# vichaarak.net
KiCad netlist of a schematic drawn in EAGLE
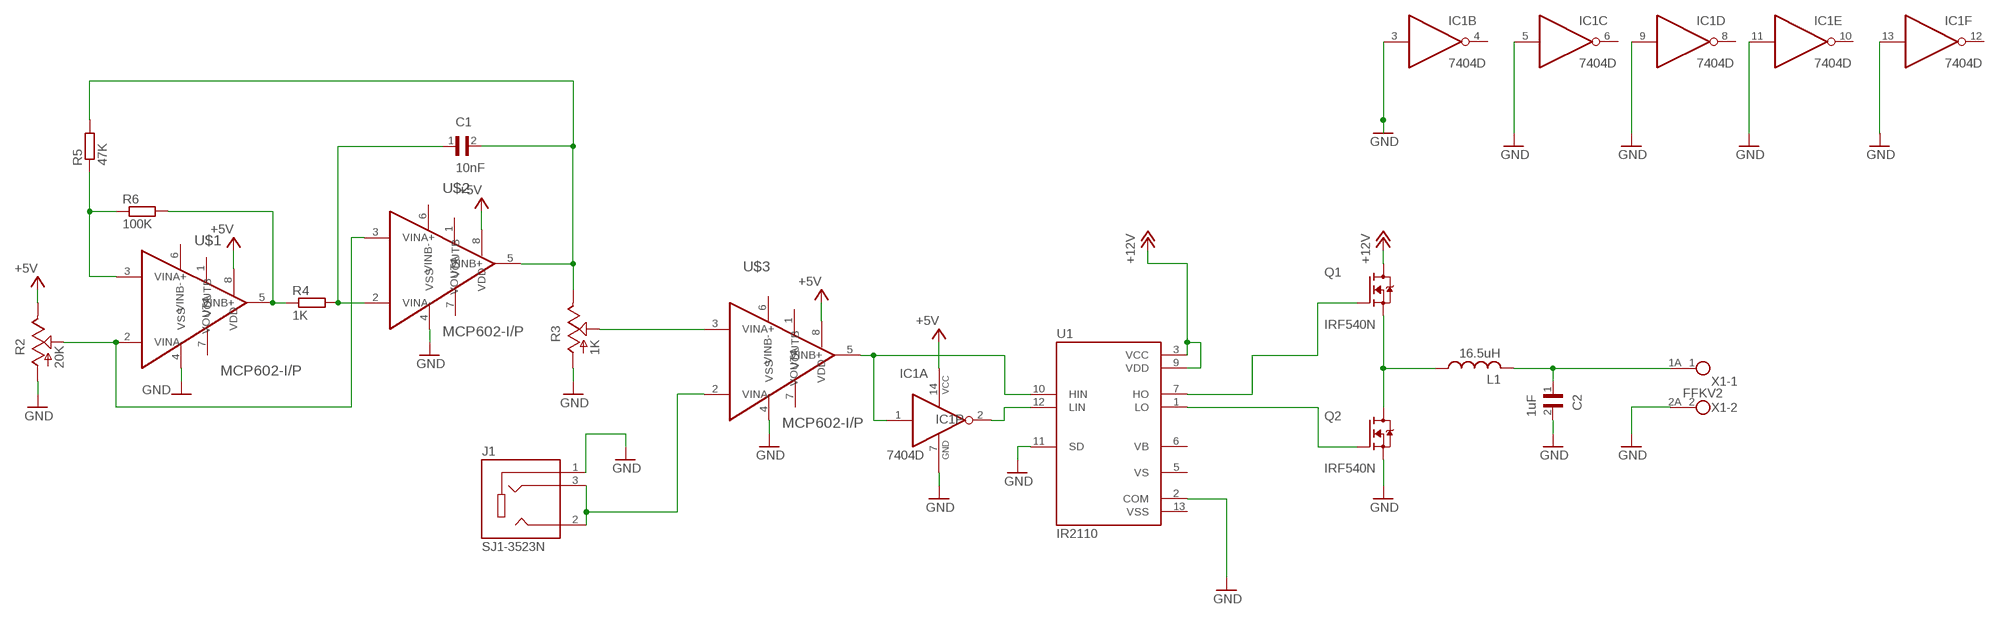
[diagram p0: schematic, sheet 1]

(export (version "E")
  (design (tool "Eeschema 10.0.6"))
  (components
    (comp (ref "C1")
      (value "10nF")
      (footprint "eagle-import:C0603")
      (fields (field (name "MF") "TDK") (field (name "MP") "CGA3E2X7R1H104K080AA"))
      (libsource (lib "eagle-import") (part "CAPACITOR"))
    )
    (comp (ref "C2")
      (value "1uF")
      (footprint "eagle-import:C0603")
      (fields (field (name "MF") "TDK") (field (name "MP") "CGA3E2X7R1H104K080AA"))
      (libsource (lib "eagle-import") (part "CAPACITOR"))
    )
    (comp (ref "IC1")
      (value "7404D")
      (footprint "eagle-import:SO14")
      (libsource (lib "eagle-import") (part "7404D"))
    )
    (comp (ref "J1")
      (value "SJ1-3523N")
      (footprint "eagle-import:CUI_SJ1-3523N")
      (fields (field (name "MF") "Same Sky"))
      (libsource (lib "eagle-import") (part "SJ1-3523N"))
    )
    (comp (ref "L1")
      (value "16.5uH")
      (footprint "eagle-import:0204_7")
      (libsource (lib "eagle-import") (part "L-US0204/7"))
    )
    (comp (ref "Q1")
      (value "IRF540N")
      (footprint "eagle-import:TO254P1054X469X1930-3")
      (fields (field (name "MF") "Infineon Technologies"))
      (libsource (lib "eagle-import") (part "IRF540N"))
    )
    (comp (ref "Q2")
      (value "IRF540N")
      (footprint "eagle-import:TO254P1054X469X1930-3")
      (fields (field (name "MF") "Infineon Technologies"))
      (libsource (lib "eagle-import") (part "IRF540N"))
    )
    (comp (ref "R2")
      (value "20K")
      (footprint "eagle-import:PT-10")
      (libsource (lib "eagle-import") (part "TRIM_US-PT10"))
    )
    (comp (ref "R3")
      (value "1K")
      (footprint "eagle-import:PT-10")
      (libsource (lib "eagle-import") (part "TRIM_US-PT10"))
    )
    (comp (ref "R4")
      (value "1K")
      (footprint "eagle-import:R0603")
      (fields (field (name "MF") "Yageo"))
      (libsource (lib "eagle-import") (part "RESISTOR"))
    )
    (comp (ref "R5")
      (value "47K")
      (footprint "eagle-import:R0603")
      (fields (field (name "MF") "Yageo"))
      (libsource (lib "eagle-import") (part "RESISTOR"))
    )
    (comp (ref "R6")
      (value "100K")
      (footprint "eagle-import:R0603")
      (fields (field (name "MF") "Yageo"))
      (libsource (lib "eagle-import") (part "RESISTOR"))
    )
    (comp (ref "U$1")
      (value "MCP602-I/P")
      (footprint "eagle-import:DIP787W46P254L927H533Q8")
      (fields (field (name "MF") "Microchip Technology"))
      (libsource (lib "eagle-import") (part "MCP602-I/P"))
    )
    (comp (ref "U$2")
      (value "MCP602-I/P")
      (footprint "eagle-import:DIP787W46P254L927H533Q8")
      (fields (field (name "MF") "Microchip Technology"))
      (libsource (lib "eagle-import") (part "MCP602-I/P"))
    )
    (comp (ref "U$3")
      (value "MCP602-I/P")
      (footprint "eagle-import:DIP787W46P254L927H533Q8")
      (fields (field (name "MF") "Microchip Technology"))
      (libsource (lib "eagle-import") (part "MCP602-I/P"))
    )
    (comp (ref "U1")
      (value "IR2110")
      (footprint "eagle-import:DIP762W45P254L2019H533Q14")
      (fields (field (name "MF") "Infineon"))
      (libsource (lib "eagle-import") (part "IR2110"))
    )
    (comp (ref "X1")
      (value "FFKV2")
      (footprint "eagle-import:FFKV2")
      (libsource (lib "eagle-import") (part "FFKV2"))
    )
  )
  (nets
    (net (code "1") (name "+5V") (class "Default")
      (node (ref "IC1") (pin "14") (pinfunction "VCC_14") (pintype "power_in"))
      (node (ref "R2") (pin "E") (pinfunction "E_E") (pintype "passive"))
      (node (ref "U$1") (pin "8") (pinfunction "VDD_8") (pintype "power_in"))
      (node (ref "U$2") (pin "8") (pinfunction "VDD_8") (pintype "power_in"))
      (node (ref "U$3") (pin "8") (pinfunction "VDD_8") (pintype "power_in"))
    )
    (net (code "2") (name "+12V") (class "Default")
      (node (ref "Q1") (pin "2") (pinfunction "D_2") (pintype "passive"))
      (node (ref "U1") (pin "3") (pinfunction "VCC_3") (pintype "power_in"))
      (node (ref "U1") (pin "9") (pinfunction "VDD_9") (pintype "power_in"))
    )
    (net (code "3") (name "/VSS") (class "Default")
      (node (ref "U1") (pin "13") (pinfunction "VSS_13") (pintype "power_in"))
    )
    (net (code "4") (name "GND") (class "Default")
      (node (ref "C2") (pin "2") (pinfunction "2_2") (pintype "passive"))
      (node (ref "IC1") (pin "11") (pinfunction "I_11") (pintype "input"))
      (node (ref "IC1") (pin "13") (pinfunction "I_13") (pintype "input"))
      (node (ref "IC1") (pin "3") (pinfunction "I_3") (pintype "input"))
      (node (ref "IC1") (pin "5") (pinfunction "I_5") (pintype "input"))
      (node (ref "IC1") (pin "7") (pinfunction "GND_7") (pintype "power_in"))
      (node (ref "IC1") (pin "9") (pinfunction "I_9") (pintype "input"))
      (node (ref "J1") (pin "1") (pinfunction "1_1") (pintype "passive"))
      (node (ref "Q2") (pin "3") (pinfunction "S_3") (pintype "passive"))
      (node (ref "R2") (pin "A") (pinfunction "A_A") (pintype "passive"))
      (node (ref "R3") (pin "A") (pinfunction "A_A") (pintype "passive"))
      (node (ref "U$1") (pin "4") (pinfunction "VSS_4") (pintype "power_in"))
      (node (ref "U$2") (pin "4") (pinfunction "VSS_4") (pintype "power_in"))
      (node (ref "U$3") (pin "4") (pinfunction "VSS_4") (pintype "power_in"))
      (node (ref "U1") (pin "11") (pinfunction "SD_11") (pintype "input"))
      (node (ref "U1") (pin "2") (pinfunction "COM_2") (pintype "power_in"))
      (node (ref "X1") (pin "2A") (pinfunction "2_2A") (pintype "passive"))
    )
    (net (code "5") (name "Net-(IC1A-I)") (class "Default")
      (node (ref "IC1") (pin "1") (pinfunction "I_1") (pintype "input"))
      (node (ref "U$3") (pin "5") (pinfunction "VINB+_5") (pintype "input"))
      (node (ref "U1") (pin "10") (pinfunction "HIN_10") (pintype "input"))
    )
    (net (code "6") (name "Net-(IC1A-O)") (class "Default")
      (node (ref "IC1") (pin "2") (pinfunction "O_2") (pintype "output"))
      (node (ref "U1") (pin "12") (pinfunction "LIN_12") (pintype "input"))
    )
    (net (code "7") (name "Net-(Q1-G)") (class "Default")
      (node (ref "Q1") (pin "1") (pinfunction "G_1") (pintype "passive"))
      (node (ref "U1") (pin "7") (pinfunction "HO_7") (pintype "output"))
    )
    (net (code "8") (name "Net-(Q1-S)") (class "Default")
      (node (ref "L1") (pin "1") (pinfunction "1_1") (pintype "passive"))
      (node (ref "Q1") (pin "3") (pinfunction "S_3") (pintype "passive"))
      (node (ref "Q2") (pin "2") (pinfunction "D_2") (pintype "passive"))
    )
    (net (code "9") (name "Net-(Q2-G)") (class "Default")
      (node (ref "Q2") (pin "1") (pinfunction "G_1") (pintype "passive"))
      (node (ref "U1") (pin "1") (pinfunction "LO_1") (pintype "output"))
    )
    (net (code "10") (name "Net-(U$1-VINA+)") (class "Default")
      (node (ref "R5") (pin "1") (pinfunction "1_1") (pintype "passive"))
      (node (ref "R6") (pin "1") (pinfunction "1_1") (pintype "passive"))
      (node (ref "U$1") (pin "3") (pinfunction "VINA+_3") (pintype "input"))
    )
    (net (code "11") (name "Net-(U$1-VINA-)") (class "Default")
      (node (ref "R2") (pin "S") (pinfunction "S_S") (pintype "passive"))
      (node (ref "U$1") (pin "2") (pinfunction "VINA-_2") (pintype "input"))
      (node (ref "U$2") (pin "3") (pinfunction "VINA+_3") (pintype "input"))
    )
    (net (code "12") (name "Net-(U$1-VINB+)") (class "Default")
      (node (ref "R4") (pin "1") (pinfunction "1_1") (pintype "passive"))
      (node (ref "R6") (pin "2") (pinfunction "2_2") (pintype "passive"))
      (node (ref "U$1") (pin "5") (pinfunction "VINB+_5") (pintype "input"))
    )
    (net (code "13") (name "Net-(U$2-VINA-)") (class "Default")
      (node (ref "C1") (pin "1") (pinfunction "1_1") (pintype "passive"))
      (node (ref "R4") (pin "2") (pinfunction "2_2") (pintype "passive"))
      (node (ref "U$2") (pin "2") (pinfunction "VINA-_2") (pintype "input"))
    )
    (net (code "14") (name "Net-(U$2-VINB+)") (class "Default")
      (node (ref "C1") (pin "2") (pinfunction "2_2") (pintype "passive"))
      (node (ref "R3") (pin "E") (pinfunction "E_E") (pintype "passive"))
      (node (ref "R5") (pin "2") (pinfunction "2_2") (pintype "passive"))
      (node (ref "U$2") (pin "5") (pinfunction "VINB+_5") (pintype "input"))
    )
    (net (code "15") (name "Net-(U$3-VINA+)") (class "Default")
      (node (ref "R3") (pin "S") (pinfunction "S_S") (pintype "passive"))
      (node (ref "U$3") (pin "3") (pinfunction "VINA+_3") (pintype "input"))
    )
    (net (code "16") (name "Net-(U$3-VINA-)") (class "Default")
      (node (ref "J1") (pin "2") (pinfunction "2_2") (pintype "passive"))
      (node (ref "J1") (pin "3") (pinfunction "3_3") (pintype "passive"))
      (node (ref "U$3") (pin "2") (pinfunction "VINA-_2") (pintype "input"))
    )
    (net (code "17") (name "Net-(X1A-2)") (class "Default")
      (node (ref "C2") (pin "1") (pinfunction "1_1") (pintype "passive"))
      (node (ref "L1") (pin "2") (pinfunction "2_2") (pintype "passive"))
      (node (ref "X1") (pin "1A") (pinfunction "2_1A") (pintype "passive"))
    )
    (net (code "18") (name "unconnected-(IC1B-O-Pad4)") (class "Default")
      (node (ref "IC1") (pin "4") (pinfunction "O_4") (pintype "output"))
    )
    (net (code "19") (name "unconnected-(IC1C-O-Pad6)") (class "Default")
      (node (ref "IC1") (pin "6") (pinfunction "O_6") (pintype "output"))
    )
    (net (code "20") (name "unconnected-(IC1D-O-Pad8)") (class "Default")
      (node (ref "IC1") (pin "8") (pinfunction "O_8") (pintype "output"))
    )
    (net (code "21") (name "unconnected-(IC1E-O-Pad10)") (class "Default")
      (node (ref "IC1") (pin "10") (pinfunction "O_10") (pintype "output"))
    )
    (net (code "22") (name "unconnected-(IC1F-O-Pad12)") (class "Default")
      (node (ref "IC1") (pin "12") (pinfunction "O_12") (pintype "output"))
    )
    (net (code "23") (name "unconnected-(U$1-VINB--Pad6)") (class "Default")
      (node (ref "U$1") (pin "6") (pinfunction "VINB-_6") (pintype "input"))
    )
    (net (code "24") (name "unconnected-(U$1-VOUTA-Pad1)") (class "Default")
      (node (ref "U$1") (pin "1") (pinfunction "VOUTA_1") (pintype "output"))
    )
    (net (code "25") (name "unconnected-(U$1-VOUTB-Pad7)") (class "Default")
      (node (ref "U$1") (pin "7") (pinfunction "VOUTB_7") (pintype "output"))
    )
    (net (code "26") (name "unconnected-(U$2-VINB--Pad6)") (class "Default")
      (node (ref "U$2") (pin "6") (pinfunction "VINB-_6") (pintype "input"))
    )
    (net (code "27") (name "unconnected-(U$2-VOUTA-Pad1)") (class "Default")
      (node (ref "U$2") (pin "1") (pinfunction "VOUTA_1") (pintype "output"))
    )
    (net (code "28") (name "unconnected-(U$2-VOUTB-Pad7)") (class "Default")
      (node (ref "U$2") (pin "7") (pinfunction "VOUTB_7") (pintype "output"))
    )
    (net (code "29") (name "unconnected-(U$3-VINB--Pad6)") (class "Default")
      (node (ref "U$3") (pin "6") (pinfunction "VINB-_6") (pintype "input"))
    )
    (net (code "30") (name "unconnected-(U$3-VOUTA-Pad1)") (class "Default")
      (node (ref "U$3") (pin "1") (pinfunction "VOUTA_1") (pintype "output"))
    )
    (net (code "31") (name "unconnected-(U$3-VOUTB-Pad7)") (class "Default")
      (node (ref "U$3") (pin "7") (pinfunction "VOUTB_7") (pintype "output"))
    )
    (net (code "32") (name "unconnected-(U1-VB-Pad6)") (class "Default")
      (node (ref "U1") (pin "6") (pinfunction "VB_6") (pintype "passive"))
    )
    (net (code "33") (name "unconnected-(U1-VS-Pad5)") (class "Default")
      (node (ref "U1") (pin "5") (pinfunction "VS_5") (pintype "passive"))
    )
    (net (code "34") (name "unconnected-(X1-Pad1)") (class "Default")
      (node (ref "X1") (pin "1") (pinfunction "1_1") (pintype "passive"))
    )
    (net (code "35") (name "unconnected-(X1B-1-Pad2)") (class "Default")
      (node (ref "X1") (pin "2") (pinfunction "1_2") (pintype "passive"))
    )
  )
)
